# Transistor_GPIO.net
KiCad netlist of a schematic drawn in EAGLE
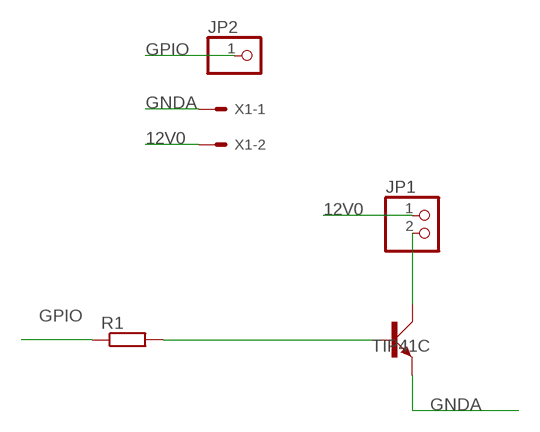
[diagram p0: schematic, sheet 1]

(export (version "E")
  (design (tool "Eeschema 10.0.6"))
  (components
    (comp (ref "JP1")
      (value "PINHD-1X2")
      (footprint "eagle-import:1X02")
      (libsource (lib "eagle-import") (part "PINHD-1X2"))
    )
    (comp (ref "JP2")
      (value "PINHD-1X1")
      (footprint "eagle-import:1X01")
      (libsource (lib "eagle-import") (part "PINHD-1X1"))
    )
    (comp (ref "Q1")
      (value "TIP41C")
      (footprint "eagle-import:TO220AV")
      (libsource (lib "eagle-import") (part "TIP41C"))
    )
    (comp (ref "R1")
      (value "R-EU_0207/10")
      (footprint "eagle-import:0207_10")
      (libsource (lib "eagle-import") (part "R-EU_0207/10"))
    )
    (comp (ref "X1")
      (value "KK-156-2")
      (footprint "eagle-import:KK-156-2")
      (fields (field (name "MF") "MOLEX"))
      (libsource (lib "eagle-import") (part "KK-156-2"))
    )
  )
  (nets
    (net (code "1") (name "/12V0") (class "Default")
      (node (ref "JP1") (pin "1") (pinfunction "1_1") (pintype "passive"))
      (node (ref "X1") (pin "2") (pinfunction "S_2") (pintype "passive"))
    )
    (net (code "2") (name "/GNDA") (class "Default")
      (node (ref "Q1") (pin "E") (pinfunction "E_E") (pintype "passive"))
      (node (ref "X1") (pin "1") (pinfunction "S_1") (pintype "passive"))
    )
    (net (code "3") (name "/GPIO") (class "Default")
      (node (ref "JP2") (pin "1") (pinfunction "1_1") (pintype "passive"))
      (node (ref "R1") (pin "1") (pinfunction "1_1") (pintype "passive"))
    )
    (net (code "4") (name "Net-(JP1-Pad2)") (class "Default")
      (node (ref "JP1") (pin "2") (pinfunction "2_2") (pintype "passive"))
      (node (ref "Q1") (pin "C") (pinfunction "C_C") (pintype "passive"))
    )
    (net (code "5") (name "Net-(Q1-PadB)") (class "Default")
      (node (ref "Q1") (pin "B") (pinfunction "B_B") (pintype "passive"))
      (node (ref "R1") (pin "2") (pinfunction "2_2") (pintype "passive"))
    )
  )
)
